# EMI_Prot.net
KiCad netlist of a schematic drawn in Altium Designer
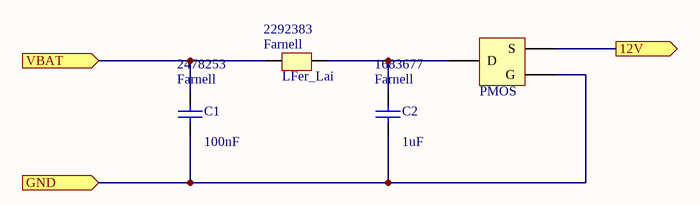
[diagram p0: EMI_Prot.SchDoc]

(export (version "E")
  (design (tool "Eeschema 10.0.6"))
  (components
    (comp (ref "C1")
      (value "100nF")
      (footprint "CAP_0805")
      (description "Capacitor")
      (fields
        (field (name "SUPPLIER 1") "Farnell")
        (field (name "SUPPLIER PART NUMBER 1") "2478253")
        (field (name "Comment") "100n")
        (field (name "PUBLISHER") "Altium Limited")
      )
      (libsource (lib "Miscellaneous Devices") (part "Cap Semi"))
    )
    (comp (ref "C2")
      (value "1uF")
      (footprint "CAP_0805")
      (description "Capacitor")
      (fields
        (field (name "SUPPLIER 1") "Farnell")
        (field (name "SUPPLIER PART NUMBER 1") "1683677")
        (field (name "Comment") "1u")
        (field (name "PUBLISHER") "Altium Limited")
      )
      (libsource (lib "Miscellaneous Devices") (part "Cap Semi"))
    )
    (comp (ref "LFer_Lai")
      (value "~")
      (footprint "LFerrite_Laird")
      (description "Laird ferrite chip bead")
      (fields (field (name "SUPPLIER 1") "Farnell") (field (name "SUPPLIER PART NUMBER 1") "2292383"))
      (libsource (lib "Schlib1_HMI3D") (part "LFerrite_Laird"))
    )
    (comp (ref "PMOS")
      (value "~")
      (footprint "PMOS")
      (description "P channel Mosfet")
      (libsource (lib "Schlib1_HMI3D") (part "PMOS"))
    )
  )
  (nets
    (net (code "1") (name "/12V") (class "Default")
      (node (ref "PMOS") (pin "S") (pinfunction "S_S") (pintype "passive"))
    )
    (net (code "2") (name "/GND") (class "Default")
      (node (ref "C1") (pin "2") (pinfunction "2_2") (pintype "passive"))
      (node (ref "C2") (pin "2") (pinfunction "2_2") (pintype "passive"))
      (node (ref "PMOS") (pin "G") (pinfunction "G_G") (pintype "passive"))
    )
    (net (code "3") (name "/VBAT") (class "Default")
      (node (ref "C1") (pin "1") (pinfunction "1_1") (pintype "passive"))
      (node (ref "LFer_Lai") (pin "1") (pinfunction "1_1") (pintype "passive"))
    )
    (net (code "4") (name "Net-(C2-Pad1)") (class "Default")
      (node (ref "C2") (pin "1") (pinfunction "1_1") (pintype "passive"))
      (node (ref "LFer_Lai") (pin "2") (pinfunction "2_2") (pintype "passive"))
      (node (ref "PMOS") (pin "D") (pinfunction "D_D") (pintype "passive"))
    )
  )
)
